# Metro_Mini_Rev_B.net
KiCad netlist of a schematic drawn in EAGLE
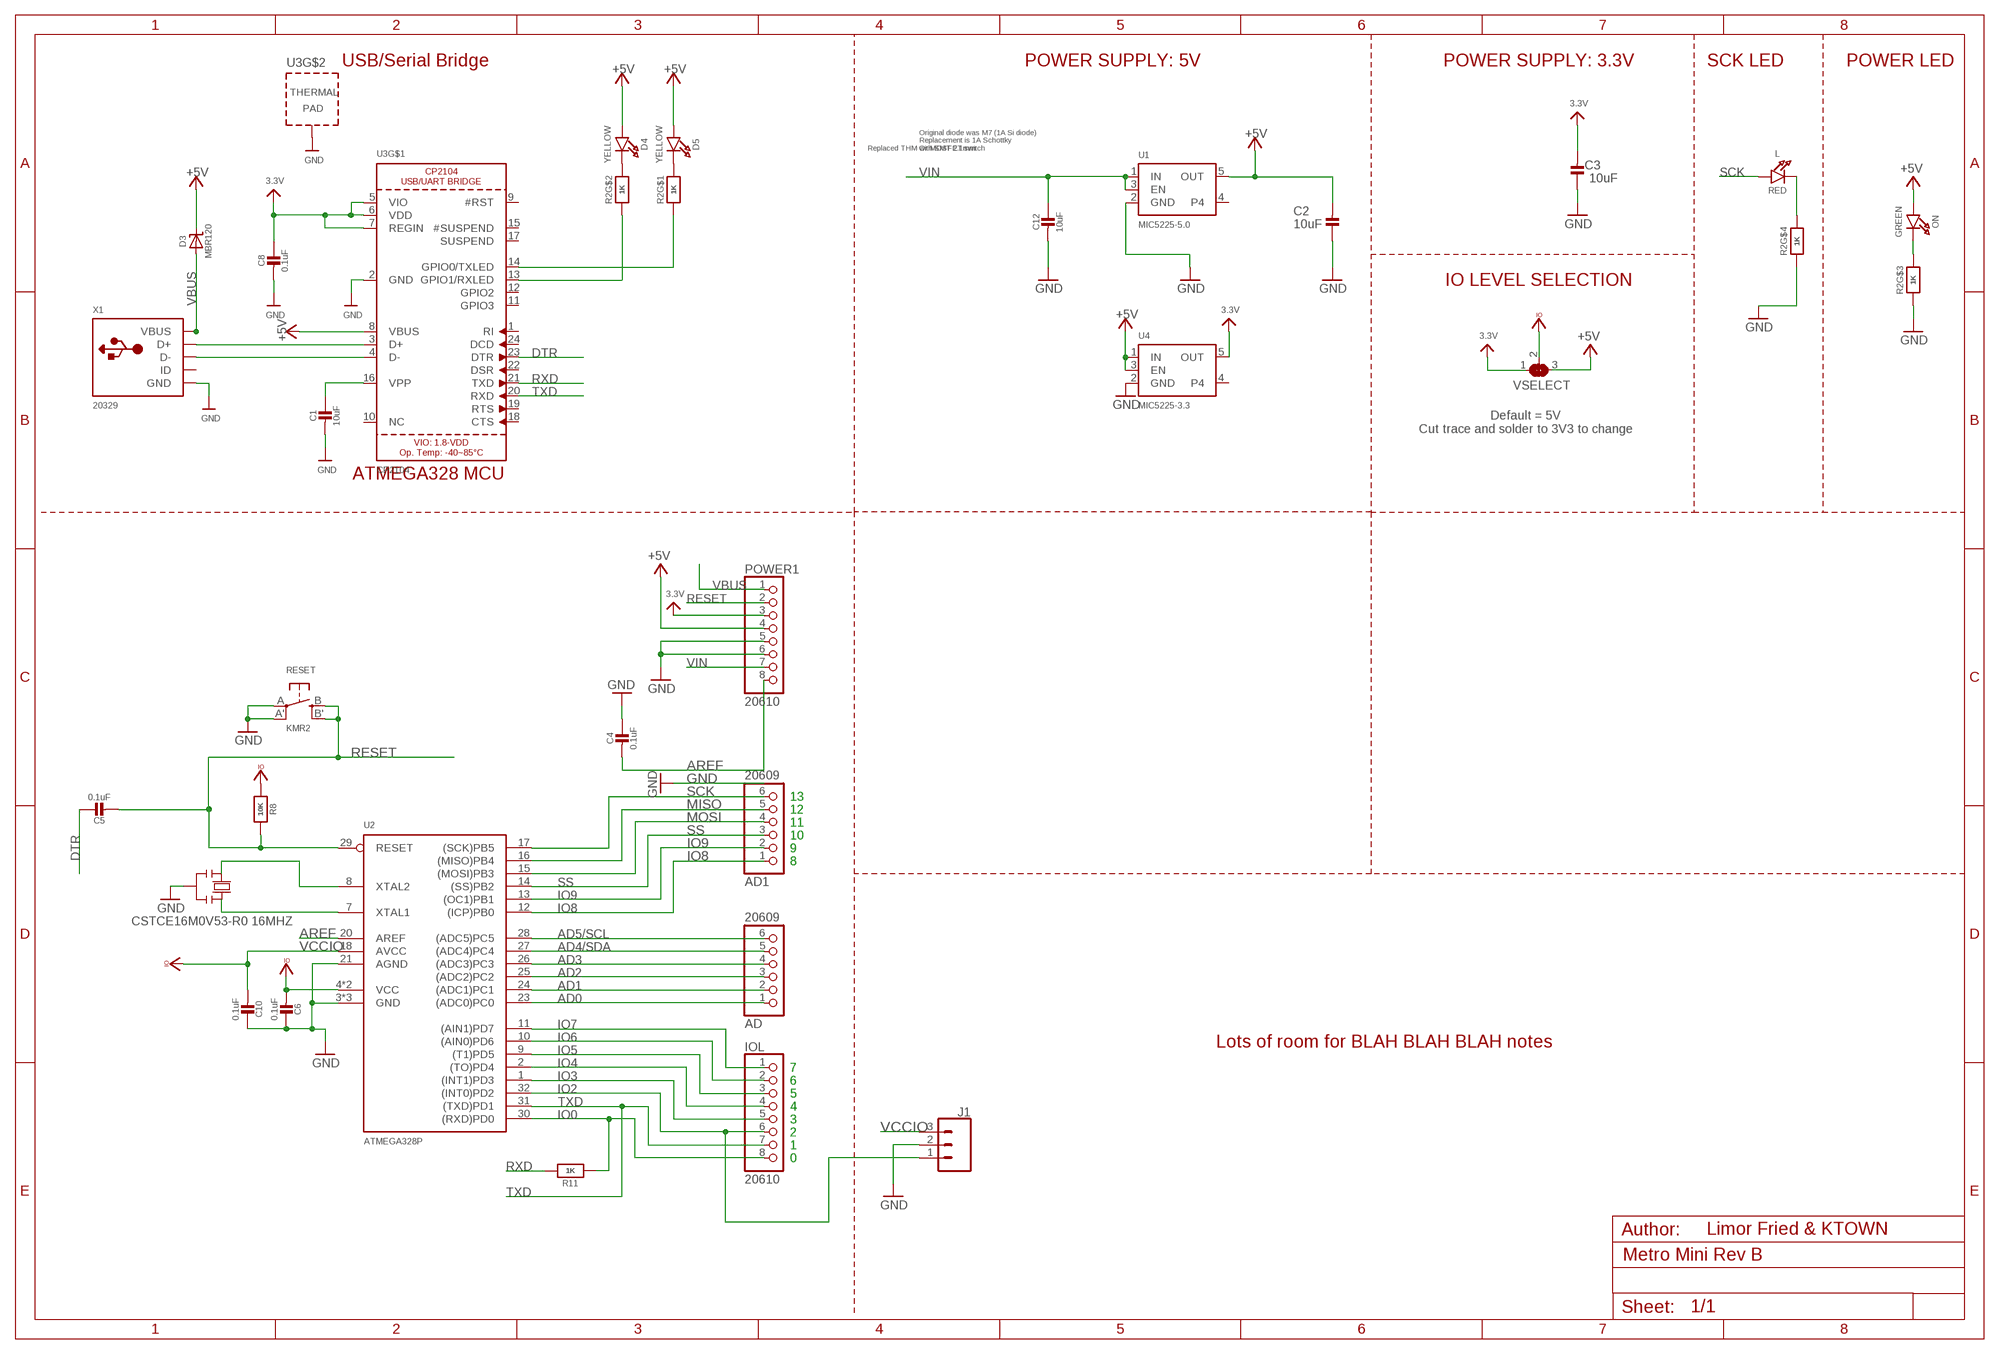
[diagram p0: schematic, sheet 1]

(export (version "E")
  (design (tool "Eeschema 10.0.6"))
  (components
    (comp (ref "AD")
      (value "20609")
      (footprint "eagle-import:1X06_ROUND")
      (libsource (lib "eagle-import") (part "HEADER-1X6ROUND"))
    )
    (comp (ref "AD1")
      (value "20609")
      (footprint "eagle-import:1X06_ROUND")
      (libsource (lib "eagle-import") (part "HEADER-1X6ROUND"))
    )
    (comp (ref "C1")
      (value "10uF")
      (footprint "eagle-import:0805-NO")
      (libsource (lib "eagle-import") (part "CAP_CERAMIC0805-NOOUTLINE"))
    )
    (comp (ref "C2")
      (value "10uF")
      (footprint "eagle-import:0805-NO")
      (libsource (lib "eagle-import") (part "CAP_CERAMIC0805-NOOUTLINE"))
    )
    (comp (ref "C3")
      (value "10uF")
      (footprint "eagle-import:0805-NO")
      (libsource (lib "eagle-import") (part "CAP_CERAMIC0805-NOOUTLINE"))
    )
    (comp (ref "C4")
      (value "0.1uF")
      (footprint "eagle-import:0805-NO")
      (libsource (lib "eagle-import") (part "CAP_CERAMIC0805-NOOUTLINE"))
    )
    (comp (ref "C5")
      (value "0.1uF")
      (footprint "eagle-import:_0805MP")
      (libsource (lib "eagle-import") (part "CAP_CERAMIC_0805MP"))
    )
    (comp (ref "C6")
      (value "0.1uF")
      (footprint "eagle-import:0805-NO")
      (libsource (lib "eagle-import") (part "CAP_CERAMIC0805-NOOUTLINE"))
    )
    (comp (ref "C8")
      (value "0.1uF")
      (footprint "eagle-import:0805-NO")
      (libsource (lib "eagle-import") (part "CAP_CERAMIC0805-NOOUTLINE"))
    )
    (comp (ref "C10")
      (value "0.1uF")
      (footprint "eagle-import:0805-NO")
      (libsource (lib "eagle-import") (part "CAP_CERAMIC0805-NOOUTLINE"))
    )
    (comp (ref "C12")
      (value "10uF")
      (footprint "eagle-import:0805-NO")
      (libsource (lib "eagle-import") (part "CAP_CERAMIC0805-NOOUTLINE"))
    )
    (comp (ref "D3")
      (value "MBR120")
      (footprint "eagle-import:SOD-123")
      (libsource (lib "eagle-import") (part "DIODE-SCHOTTKYSOD-123"))
    )
    (comp (ref "D4")
      (value "YELLOW")
      (footprint "eagle-import:CHIPLED_0805_NOOUTLINE")
      (libsource (lib "eagle-import") (part "LED0805_NOOUTLINE"))
    )
    (comp (ref "D5")
      (value "YELLOW")
      (footprint "eagle-import:CHIPLED_0805_NOOUTLINE")
      (libsource (lib "eagle-import") (part "LED0805_NOOUTLINE"))
    )
    (comp (ref "IOL")
      (value "20610")
      (footprint "eagle-import:1X08_ROUND")
      (libsource (lib "eagle-import") (part "HEADER-1X8ROUND"))
    )
    (comp (ref "J1")
      (value "CONN_03")
      (footprint "eagle-import:1X03")
      (libsource (lib "eagle-import") (part "CONN_03"))
    )
    (comp (ref "L")
      (value "RED")
      (footprint "eagle-import:CHIPLED_0805_NOOUTLINE")
      (libsource (lib "eagle-import") (part "LED0805_NOOUTLINE"))
    )
    (comp (ref "ON")
      (value "GREEN")
      (footprint "eagle-import:CHIPLED_0805_NOOUTLINE")
      (libsource (lib "eagle-import") (part "LED0805_NOOUTLINE"))
    )
    (comp (ref "POWER1")
      (value "20610")
      (footprint "eagle-import:1X08_ROUND_70")
      (libsource (lib "eagle-import") (part "HEADER-1X870MIL"))
    )
    (comp (ref "R2")
      (value "1K")
      (footprint "eagle-import:RESPACK_4X0603")
      (libsource (lib "eagle-import") (part "RESISTOR_4PACK"))
    )
    (comp (ref "R8")
      (value "10K")
      (footprint "eagle-import:0805-NO")
      (libsource (lib "eagle-import") (part "RESISTOR0805_NOOUTLINE"))
    )
    (comp (ref "R11")
      (value "1K")
      (footprint "eagle-import:0805-NO")
      (libsource (lib "eagle-import") (part "RESISTOR0805_NOOUTLINE"))
    )
    (comp (ref "RESET")
      (value "KMR2")
      (footprint "eagle-import:BTN_KMR2_4.6X2.8")
      (libsource (lib "eagle-import") (part "SWITCH_TACT_SMT4.6X2.8"))
    )
    (comp (ref "U1")
      (value "MIC5225-5.0")
      (footprint "eagle-import:SOT23-5")
      (libsource (lib "eagle-import") (part "VREG_SOT23-5"))
    )
    (comp (ref "U2")
      (value "ATMEGA328P")
      (footprint "eagle-import:MLF32-TH")
      (libsource (lib "eagle-import") (part "ATMEGA328P"))
    )
    (comp (ref "U3")
      (value "CP2104")
      (footprint "eagle-import:QFN24_4MM_SMSC")
      (libsource (lib "eagle-import") (part "CP2104"))
    )
    (comp (ref "U4")
      (value "MIC5225-3.3")
      (footprint "eagle-import:SOT23-5")
      (libsource (lib "eagle-import") (part "VREG_SOT23-5"))
    )
    (comp (ref "VSELECT")
      (value "SOLDERJUMPER_2WAY")
      (footprint "eagle-import:SOLDERJUMPER_2WAY_OPEN_NOPASTE")
      (libsource (lib "eagle-import") (part "SOLDERJUMPER_2WAY"))
    )
    (comp (ref "X1")
      (value "20329")
      (footprint "eagle-import:4UCONN_20329_V2")
      (libsource (lib "eagle-import") (part "USB_MICRO_20329_V2"))
    )
    (comp (ref "Y2")
      (value "CSTCE16M0V53-R0 16MHZ")
      (footprint "eagle-import:RESONATOR")
      (libsource (lib "eagle-import") (part "RESONATORMU"))
    )
  )
  (nets
    (net (code "1") (name "+5V") (class "Default")
      (node (ref "C2") (pin "2") (pinfunction "2_2") (pintype "passive"))
      (node (ref "D3") (pin "C") (pinfunction "C_C") (pintype "passive"))
      (node (ref "D4") (pin "A") (pinfunction "A_A") (pintype "passive"))
      (node (ref "D5") (pin "A") (pinfunction "A_A") (pintype "passive"))
      (node (ref "ON") (pin "A") (pinfunction "A_A") (pintype "passive"))
      (node (ref "POWER1") (pin "4") (pinfunction "4_4") (pintype "passive"))
      (node (ref "U1") (pin "5") (pinfunction "OUT_5") (pintype "power_in"))
      (node (ref "U3") (pin "8") (pinfunction "VBUS_8") (pintype "power_in"))
      (node (ref "U4") (pin "1") (pinfunction "IN_1") (pintype "power_in"))
      (node (ref "U4") (pin "3") (pinfunction "EN_3") (pintype "input"))
      (node (ref "VSELECT") (pin "3") (pinfunction "3_3") (pintype "passive"))
    )
    (net (code "2") (name "/AD0") (class "Default")
      (node (ref "AD") (pin "1") (pinfunction "1_1") (pintype "passive"))
      (node (ref "U2") (pin "23") (pinfunction "(ADC0)PC0_23") (pintype "bidirectional"))
    )
    (net (code "3") (name "/AD1") (class "Default")
      (node (ref "AD") (pin "2") (pinfunction "2_2") (pintype "passive"))
      (node (ref "U2") (pin "24") (pinfunction "(ADC1)PC1_24") (pintype "bidirectional"))
    )
    (net (code "4") (name "/AD2") (class "Default")
      (node (ref "AD") (pin "3") (pinfunction "3_3") (pintype "passive"))
      (node (ref "U2") (pin "25") (pinfunction "(ADC2)PC2_25") (pintype "bidirectional"))
    )
    (net (code "5") (name "/AD3") (class "Default")
      (node (ref "AD") (pin "4") (pinfunction "4_4") (pintype "passive"))
      (node (ref "U2") (pin "26") (pinfunction "(ADC3)PC3_26") (pintype "bidirectional"))
    )
    (net (code "6") (name "/AD4{slash}SDA") (class "Default")
      (node (ref "AD") (pin "5") (pinfunction "5_5") (pintype "passive"))
      (node (ref "U2") (pin "27") (pinfunction "(ADC4)PC4_27") (pintype "bidirectional"))
    )
    (net (code "7") (name "/AD5{slash}SCL") (class "Default")
      (node (ref "AD") (pin "6") (pinfunction "6_6") (pintype "passive"))
      (node (ref "U2") (pin "28") (pinfunction "(ADC5)PC5_28") (pintype "bidirectional"))
    )
    (net (code "8") (name "/AREF") (class "Default")
      (node (ref "C4") (pin "2") (pinfunction "2_2") (pintype "passive"))
      (node (ref "POWER1") (pin "8") (pinfunction "8_8") (pintype "passive"))
      (node (ref "U2") (pin "20") (pinfunction "AREF_20") (pintype "power_in"))
    )
    (net (code "9") (name "/DTR") (class "Default")
      (node (ref "C5") (pin "1") (pinfunction "1_1") (pintype "passive"))
      (node (ref "U3") (pin "23") (pinfunction "DTR_23") (pintype "output"))
    )
    (net (code "10") (name "/IO0") (class "Default")
      (node (ref "IOL") (pin "8") (pinfunction "8_8") (pintype "passive"))
      (node (ref "R11") (pin "1") (pinfunction "1_1") (pintype "passive"))
      (node (ref "U2") (pin "30") (pinfunction "(RXD)PD0_30") (pintype "bidirectional"))
    )
    (net (code "11") (name "/IO2") (class "Default")
      (node (ref "IOL") (pin "6") (pinfunction "6_6") (pintype "passive"))
      (node (ref "J1") (pin "1") (pinfunction "1_1") (pintype "passive"))
      (node (ref "U2") (pin "32") (pinfunction "(INT0)PD2_32") (pintype "bidirectional"))
    )
    (net (code "12") (name "/IO3") (class "Default")
      (node (ref "IOL") (pin "5") (pinfunction "5_5") (pintype "passive"))
      (node (ref "U2") (pin "1") (pinfunction "(INT1)PD3_1") (pintype "bidirectional"))
    )
    (net (code "13") (name "/IO4") (class "Default")
      (node (ref "IOL") (pin "4") (pinfunction "4_4") (pintype "passive"))
      (node (ref "U2") (pin "2") (pinfunction "(TO)PD4_2") (pintype "bidirectional"))
    )
    (net (code "14") (name "/IO5") (class "Default")
      (node (ref "IOL") (pin "3") (pinfunction "3_3") (pintype "passive"))
      (node (ref "U2") (pin "9") (pinfunction "(T1)PD5_9") (pintype "bidirectional"))
    )
    (net (code "15") (name "/IO6") (class "Default")
      (node (ref "IOL") (pin "2") (pinfunction "2_2") (pintype "passive"))
      (node (ref "U2") (pin "10") (pinfunction "(AIN0)PD6_10") (pintype "bidirectional"))
    )
    (net (code "16") (name "/IO7") (class "Default")
      (node (ref "IOL") (pin "1") (pinfunction "1_1") (pintype "passive"))
      (node (ref "U2") (pin "11") (pinfunction "(AIN1)PD7_11") (pintype "bidirectional"))
    )
    (net (code "17") (name "/IO8") (class "Default")
      (node (ref "AD1") (pin "1") (pinfunction "1_1") (pintype "passive"))
      (node (ref "U2") (pin "12") (pinfunction "(ICP)PB0_12") (pintype "bidirectional"))
    )
    (net (code "18") (name "/IO9") (class "Default")
      (node (ref "AD1") (pin "2") (pinfunction "2_2") (pintype "passive"))
      (node (ref "U2") (pin "13") (pinfunction "(OC1)PB1_13") (pintype "bidirectional"))
    )
    (net (code "19") (name "/MISO") (class "Default")
      (node (ref "AD1") (pin "5") (pinfunction "5_5") (pintype "passive"))
      (node (ref "U2") (pin "16") (pinfunction "(MISO)PB4_16") (pintype "bidirectional"))
    )
    (net (code "20") (name "/MOSI") (class "Default")
      (node (ref "AD1") (pin "4") (pinfunction "4_4") (pintype "passive"))
      (node (ref "U2") (pin "15") (pinfunction "(MOSI)PB3_15") (pintype "bidirectional"))
    )
    (net (code "21") (name "/RESET") (class "Default")
      (node (ref "C5") (pin "2") (pinfunction "2_2") (pintype "passive"))
      (node (ref "POWER1") (pin "2") (pinfunction "2_2") (pintype "passive"))
      (node (ref "R8") (pin "1") (pinfunction "1_1") (pintype "passive"))
      (node (ref "RESET") (pin "B") (pinfunction "S_B") (pintype "passive"))
      (node (ref "RESET") (pin "B'") (pinfunction "S1_B'") (pintype "passive"))
      (node (ref "U2") (pin "29") (pinfunction "RESET_29") (pintype "bidirectional"))
    )
    (net (code "22") (name "/RXD") (class "Default")
      (node (ref "R11") (pin "2") (pinfunction "2_2") (pintype "passive"))
      (node (ref "U3") (pin "21") (pinfunction "TXD_21") (pintype "output"))
    )
    (net (code "23") (name "/SCK") (class "Default")
      (node (ref "AD1") (pin "6") (pinfunction "6_6") (pintype "passive"))
      (node (ref "L") (pin "A") (pinfunction "A_A") (pintype "passive"))
      (node (ref "U2") (pin "17") (pinfunction "(SCK)PB5_17") (pintype "bidirectional"))
    )
    (net (code "24") (name "/SS") (class "Default")
      (node (ref "AD1") (pin "3") (pinfunction "3_3") (pintype "passive"))
      (node (ref "U2") (pin "14") (pinfunction "(SS)PB2_14") (pintype "bidirectional"))
    )
    (net (code "25") (name "/TXD") (class "Default")
      (node (ref "IOL") (pin "7") (pinfunction "7_7") (pintype "passive"))
      (node (ref "U2") (pin "31") (pinfunction "(TXD)PD1_31") (pintype "bidirectional"))
      (node (ref "U3") (pin "20") (pinfunction "RXD_20") (pintype "input"))
    )
    (net (code "26") (name "/VBUS") (class "Default")
      (node (ref "D3") (pin "A") (pinfunction "A_A") (pintype "passive"))
      (node (ref "POWER1") (pin "1") (pinfunction "1_1") (pintype "passive"))
      (node (ref "X1") (pin "VBUS") (pinfunction "VBUS_VBUS") (pintype "power_in"))
    )
    (net (code "27") (name "/VIN") (class "Default")
      (node (ref "C12") (pin "1") (pinfunction "1_1") (pintype "passive"))
      (node (ref "POWER1") (pin "7") (pinfunction "7_7") (pintype "passive"))
      (node (ref "U1") (pin "1") (pinfunction "IN_1") (pintype "power_in"))
      (node (ref "U1") (pin "3") (pinfunction "EN_3") (pintype "input"))
    )
    (net (code "28") (name "3.3V") (class "Default")
      (node (ref "C3") (pin "2") (pinfunction "2_2") (pintype "passive"))
      (node (ref "C8") (pin "1") (pinfunction "1_1") (pintype "passive"))
      (node (ref "POWER1") (pin "3") (pinfunction "3_3") (pintype "passive"))
      (node (ref "U3") (pin "5") (pinfunction "VIO_5") (pintype "power_in"))
      (node (ref "U3") (pin "6") (pinfunction "VDD_6") (pintype "power_in"))
      (node (ref "U3") (pin "7") (pinfunction "REGIN_7") (pintype "power_in"))
      (node (ref "U4") (pin "5") (pinfunction "OUT_5") (pintype "power_in"))
      (node (ref "VSELECT") (pin "1") (pinfunction "1_1") (pintype "passive"))
    )
    (net (code "29") (name "GND") (class "Default")
      (node (ref "C1") (pin "2") (pinfunction "2_2") (pintype "passive"))
      (node (ref "C10") (pin "1") (pinfunction "1_1") (pintype "passive"))
      (node (ref "C12") (pin "2") (pinfunction "2_2") (pintype "passive"))
      (node (ref "C2") (pin "1") (pinfunction "1_1") (pintype "passive"))
      (node (ref "C3") (pin "1") (pinfunction "1_1") (pintype "passive"))
      (node (ref "C4") (pin "1") (pinfunction "1_1") (pintype "passive"))
      (node (ref "C6") (pin "1") (pinfunction "1_1") (pintype "passive"))
      (node (ref "C8") (pin "2") (pinfunction "2_2") (pintype "passive"))
      (node (ref "J1") (pin "2") (pinfunction "2_2") (pintype "passive"))
      (node (ref "POWER1") (pin "5") (pinfunction "5_5") (pintype "passive"))
      (node (ref "POWER1") (pin "6") (pinfunction "6_6") (pintype "passive"))
      (node (ref "R2") (pin "3") (pinfunction "1_3") (pintype "passive"))
      (node (ref "R2") (pin "4") (pinfunction "1_4") (pintype "passive"))
      (node (ref "RESET") (pin "A") (pinfunction "P_A") (pintype "passive"))
      (node (ref "RESET") (pin "A'") (pinfunction "P1_A'") (pintype "passive"))
      (node (ref "U1") (pin "2") (pinfunction "GND_2") (pintype "power_in"))
      (node (ref "U2") (pin "21") (pinfunction "AGND_21") (pintype "power_in"))
      (node (ref "U2") (pin "3") (pinfunction "GND_3") (pintype "power_in"))
      (node (ref "U2") (pin "5") (pinfunction "GND_5") (pintype "power_in"))
      (node (ref "U2") (pin "TH") (pinfunction "GND_TH") (pintype "power_in"))
      (node (ref "U3") (pin "2") (pinfunction "GND_2") (pintype "power_in"))
      (node (ref "U3") (pin "THERM") (pinfunction "TP_THERM") (pintype "power_in"))
      (node (ref "U4") (pin "2") (pinfunction "GND_2") (pintype "power_in"))
      (node (ref "X1") (pin "BASE@1") (pinfunction "GND_BASE@1") (pintype "power_in"))
      (node (ref "X1") (pin "BASE@2") (pinfunction "GND_BASE@2") (pintype "power_in"))
      (node (ref "X1") (pin "GND") (pinfunction "GND_GND") (pintype "power_in"))
      (node (ref "X1") (pin "SPRT@1") (pinfunction "GND_SPRT@1") (pintype "power_in"))
      (node (ref "X1") (pin "SPRT@2") (pinfunction "GND_SPRT@2") (pintype "power_in"))
      (node (ref "X1") (pin "SPRT@3") (pinfunction "GND_SPRT@3") (pintype "power_in"))
      (node (ref "X1") (pin "SPRT@4") (pinfunction "GND_SPRT@4") (pintype "power_in"))
      (node (ref "Y2") (pin "2") (pinfunction "2_2") (pintype "passive"))
    )
    (net (code "30") (name "Net-(R2A-2)") (class "Default")
      (node (ref "D5") (pin "C") (pinfunction "C_C") (pintype "passive"))
      (node (ref "R2") (pin "8") (pinfunction "2_8") (pintype "passive"))
    )
    (net (code "31") (name "Net-(R2B-1)") (class "Default")
      (node (ref "R2") (pin "2") (pinfunction "1_2") (pintype "passive"))
      (node (ref "U3") (pin "13") (pinfunction "GPIO1/RXLED_13") (pintype "bidirectional"))
    )
    (net (code "32") (name "Net-(R2B-2)") (class "Default")
      (node (ref "D4") (pin "C") (pinfunction "C_C") (pintype "passive"))
      (node (ref "R2") (pin "7") (pinfunction "2_7") (pintype "passive"))
    )
    (net (code "33") (name "Net-(R2C-2)") (class "Default")
      (node (ref "ON") (pin "C") (pinfunction "C_C") (pintype "passive"))
      (node (ref "R2") (pin "6") (pinfunction "2_6") (pintype "passive"))
    )
    (net (code "34") (name "Net-(R2D-2)") (class "Default")
      (node (ref "L") (pin "C") (pinfunction "C_C") (pintype "passive"))
      (node (ref "R2") (pin "5") (pinfunction "2_5") (pintype "passive"))
    )
    (net (code "35") (name "Net-(U2-XTAL1)") (class "Default")
      (node (ref "U2") (pin "7") (pinfunction "XTAL1_7") (pintype "bidirectional"))
      (node (ref "Y2") (pin "3") (pinfunction "3_3") (pintype "passive"))
    )
    (net (code "36") (name "Net-(U2-XTAL2)") (class "Default")
      (node (ref "U2") (pin "8") (pinfunction "XTAL2_8") (pintype "bidirectional"))
      (node (ref "Y2") (pin "1") (pinfunction "1_1") (pintype "passive"))
    )
    (net (code "37") (name "Net-(U3A-D+)") (class "Default")
      (node (ref "U3") (pin "3") (pinfunction "D+_3") (pintype "bidirectional"))
      (node (ref "X1") (pin "D+") (pinfunction "D+_D+") (pintype "bidirectional"))
    )
    (net (code "38") (name "Net-(U3A-D-)") (class "Default")
      (node (ref "U3") (pin "4") (pinfunction "D-_4") (pintype "bidirectional"))
      (node (ref "X1") (pin "D-") (pinfunction "D-_D-") (pintype "bidirectional"))
    )
    (net (code "39") (name "Net-(U3A-GPIO0{slash}TXLED)") (class "Default")
      (node (ref "R2") (pin "1") (pinfunction "1_1") (pintype "passive"))
      (node (ref "U3") (pin "14") (pinfunction "GPIO0/TXLED_14") (pintype "bidirectional"))
    )
    (net (code "40") (name "Net-(U3A-VPP)") (class "Default")
      (node (ref "C1") (pin "1") (pinfunction "1_1") (pintype "passive"))
      (node (ref "U3") (pin "16") (pinfunction "VPP_16") (pintype "bidirectional"))
    )
    (net (code "41") (name "VCCIO") (class "Default")
      (node (ref "C10") (pin "2") (pinfunction "2_2") (pintype "passive"))
      (node (ref "C6") (pin "2") (pinfunction "2_2") (pintype "passive"))
      (node (ref "J1") (pin "3") (pinfunction "3_3") (pintype "passive"))
      (node (ref "R8") (pin "2") (pinfunction "2_2") (pintype "passive"))
      (node (ref "U2") (pin "18") (pinfunction "AVCC_18") (pintype "power_in"))
      (node (ref "U2") (pin "4") (pinfunction "VCC_4") (pintype "power_in"))
      (node (ref "U2") (pin "6") (pinfunction "VCC_6") (pintype "power_in"))
      (node (ref "VSELECT") (pin "2") (pinfunction "2_2") (pintype "passive"))
    )
    (net (code "42") (name "unconnected-(U1-P4-Pad4)") (class "Default")
      (node (ref "U1") (pin "4") (pinfunction "P4_4") (pintype "bidirectional"))
    )
    (net (code "43") (name "unconnected-(U3A-#RST-Pad9)") (class "Default")
      (node (ref "U3") (pin "9") (pinfunction "#RST_9") (pintype "bidirectional"))
    )
    (net (code "44") (name "unconnected-(U3A-#SUSPEND-Pad15)") (class "Default")
      (node (ref "U3") (pin "15") (pinfunction "#SUSPEND_15") (pintype "output"))
    )
    (net (code "45") (name "unconnected-(U3A-CTS-Pad18)") (class "Default")
      (node (ref "U3") (pin "18") (pinfunction "CTS_18") (pintype "input"))
    )
    (net (code "46") (name "unconnected-(U3A-DCD-Pad24)") (class "Default")
      (node (ref "U3") (pin "24") (pinfunction "DCD_24") (pintype "input"))
    )
    (net (code "47") (name "unconnected-(U3A-DSR-Pad22)") (class "Default")
      (node (ref "U3") (pin "22") (pinfunction "DSR_22") (pintype "input"))
    )
    (net (code "48") (name "unconnected-(U3A-GPIO2-Pad12)") (class "Default")
      (node (ref "U3") (pin "12") (pinfunction "GPIO2_12") (pintype "bidirectional"))
    )
    (net (code "49") (name "unconnected-(U3A-GPIO3-Pad11)") (class "Default")
      (node (ref "U3") (pin "11") (pinfunction "GPIO3_11") (pintype "bidirectional"))
    )
    (net (code "50") (name "unconnected-(U3A-NC-Pad10)") (class "Default")
      (node (ref "U3") (pin "10") (pinfunction "NC_10") (pintype "no_connect"))
    )
    (net (code "51") (name "unconnected-(U3A-RI-Pad1)") (class "Default")
      (node (ref "U3") (pin "1") (pinfunction "RI_1") (pintype "input"))
    )
    (net (code "52") (name "unconnected-(U3A-RTS-Pad19)") (class "Default")
      (node (ref "U3") (pin "19") (pinfunction "RTS_19") (pintype "output"))
    )
    (net (code "53") (name "unconnected-(U3A-SUSPEND-Pad17)") (class "Default")
      (node (ref "U3") (pin "17") (pinfunction "SUSPEND_17") (pintype "output"))
    )
    (net (code "54") (name "unconnected-(U4-P4-Pad4)") (class "Default")
      (node (ref "U4") (pin "4") (pinfunction "P4_4") (pintype "bidirectional"))
    )
    (net (code "55") (name "unconnected-(X1-PadID)") (class "Default")
      (node (ref "X1") (pin "ID") (pinfunction "ID_ID") (pintype "bidirectional"))
    )
  )
)
